# VL6180_Sensor.net
KiCad netlist of a schematic drawn in EAGLE
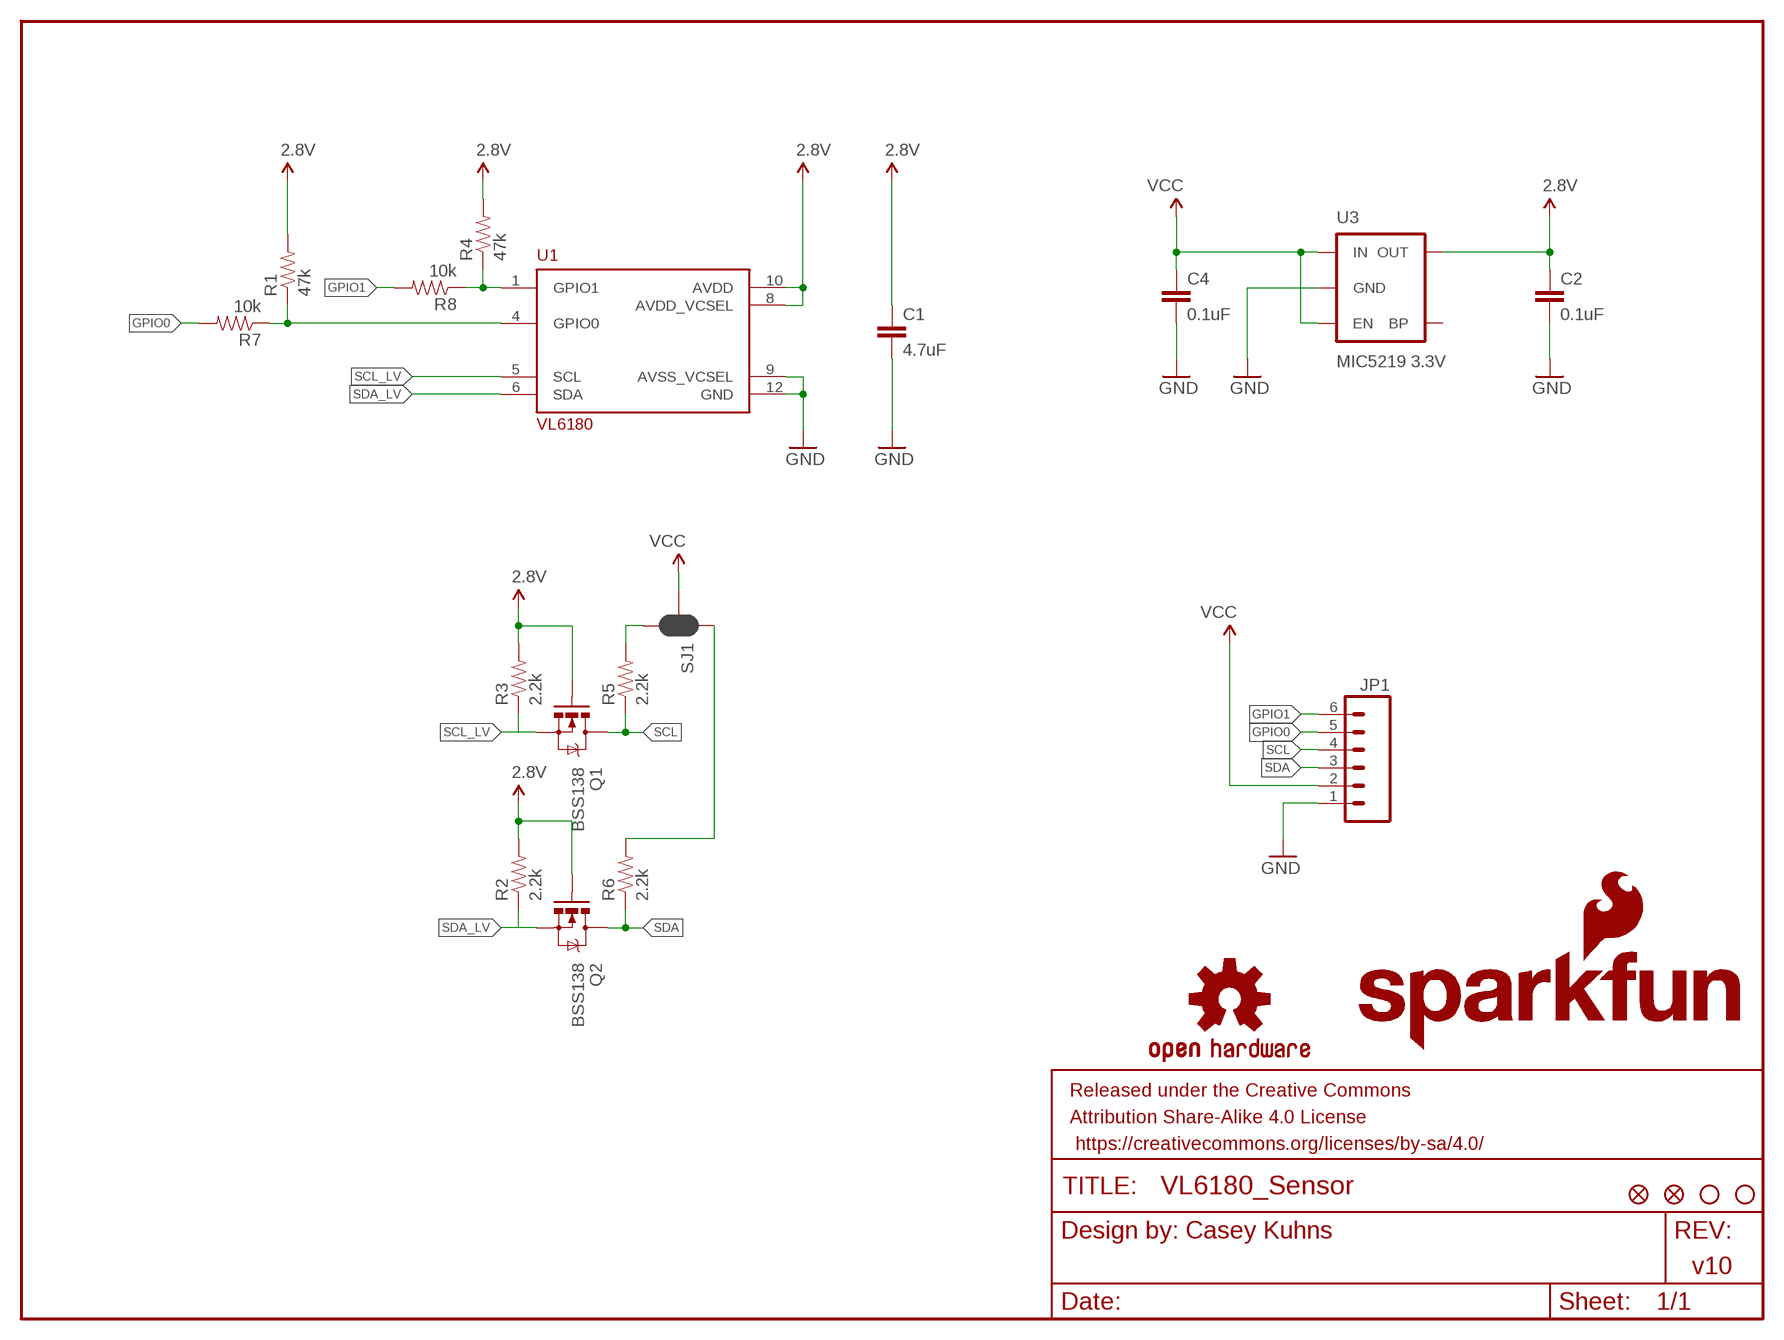
[diagram p0: schematic, sheet 1]

(export (version "E")
  (design (tool "Eeschema 10.0.6"))
  (components
    (comp (ref "C1")
      (value "4.7uF")
      (footprint "eagle-import:0603-CAP")
      (libsource (lib "eagle-import") (part "4.7UF-6.3V-10%(0603)0603"))
    )
    (comp (ref "C2")
      (value "0.1uF")
      (footprint "eagle-import:0603-CAP")
      (libsource (lib "eagle-import") (part "0.1UF-25V(+80/-20%)(0603)"))
    )
    (comp (ref "C4")
      (value "0.1uF")
      (footprint "eagle-import:0603-CAP")
      (libsource (lib "eagle-import") (part "0.1UF-25V(+80/-20%)(0603)"))
    )
    (comp (ref "FID1")
      (value "FIDUCIAL1X2")
      (footprint "eagle-import:FIDUCIAL-1X2")
      (libsource (lib "eagle-import") (part "FIDUCIAL1X2"))
    )
    (comp (ref "FID2")
      (value "FIDUCIAL1X2")
      (footprint "eagle-import:FIDUCIAL-1X2")
      (libsource (lib "eagle-import") (part "FIDUCIAL1X2"))
    )
    (comp (ref "FRAME1")
      (value "FRAME-LETTER")
      (footprint "eagle-import:CREATIVE_COMMONS")
      (libsource (lib "eagle-import") (part "FRAME-LETTER"))
    )
    (comp (ref "JP1")
      (value "M06SIP")
      (footprint "eagle-import:1X06")
      (libsource (lib "eagle-import") (part "M06SIP"))
    )
    (comp (ref "LOGO1")
      (value "SFE_LOGO_NAME_FLAME.1_INCH")
      (footprint "eagle-import:SFE_LOGO_NAME_FLAME_.1")
      (libsource (lib "eagle-import") (part "SFE_LOGO_NAME_FLAME.1_INCH"))
    )
    (comp (ref "LOGO2")
      (value "OSHW-LOGOS")
      (footprint "eagle-import:OSHW-LOGO-S")
      (libsource (lib "eagle-import") (part "OSHW-LOGOS"))
    )
    (comp (ref "Q1")
      (value "BSS138")
      (footprint "eagle-import:SOT23")
      (libsource (lib "eagle-import") (part "MOSFET-NCHANNELBSS138"))
    )
    (comp (ref "Q2")
      (value "BSS138")
      (footprint "eagle-import:SOT23")
      (libsource (lib "eagle-import") (part "MOSFET-NCHANNELBSS138"))
    )
    (comp (ref "R1")
      (value "47k")
      (footprint "eagle-import:0603-RES")
      (libsource (lib "eagle-import") (part "47KOHM1/10W1%(0603)"))
    )
    (comp (ref "R2")
      (value "2.2k")
      (footprint "eagle-import:0603-RES")
      (libsource (lib "eagle-import") (part "2.2KOHM1/10W1%(0603)"))
    )
    (comp (ref "R3")
      (value "2.2k")
      (footprint "eagle-import:0603-RES")
      (libsource (lib "eagle-import") (part "2.2KOHM1/10W1%(0603)"))
    )
    (comp (ref "R4")
      (value "47k")
      (footprint "eagle-import:0603-RES")
      (libsource (lib "eagle-import") (part "47KOHM1/10W1%(0603)"))
    )
    (comp (ref "R5")
      (value "2.2k")
      (footprint "eagle-import:0603-RES")
      (libsource (lib "eagle-import") (part "2.2KOHM1/10W1%(0603)"))
    )
    (comp (ref "R6")
      (value "2.2k")
      (footprint "eagle-import:0603-RES")
      (libsource (lib "eagle-import") (part "2.2KOHM1/10W1%(0603)"))
    )
    (comp (ref "R7")
      (value "10k")
      (footprint "eagle-import:0603-RES")
      (libsource (lib "eagle-import") (part "10KOHM1/10W1%(0603)0603"))
    )
    (comp (ref "R8")
      (value "10k")
      (footprint "eagle-import:0603-RES")
      (libsource (lib "eagle-import") (part "10KOHM1/10W1%(0603)0603"))
    )
    (comp (ref "SJ1")
      (value "JUMPER-PAD-3-NC_BY_PASTE")
      (footprint "eagle-import:PAD-JUMPER-3-NC_BY_PASTE_YES_SILK_FULL_BOX")
      (libsource (lib "eagle-import") (part "JUMPER-PAD-3-NC_BY_PASTE"))
    )
    (comp (ref "STANDOFF1")
      (value "STAND-OFF")
      (footprint "eagle-import:STAND-OFF")
      (libsource (lib "eagle-import") (part "STAND-OFF"))
    )
    (comp (ref "STANDOFF2")
      (value "STAND-OFF")
      (footprint "eagle-import:STAND-OFF")
      (libsource (lib "eagle-import") (part "STAND-OFF"))
    )
    (comp (ref "U1")
      (value "VL6180")
      (footprint "eagle-import:VL6180")
      (libsource (lib "eagle-import") (part "VL6180"))
    )
    (comp (ref "U3")
      (value "MIC5219 3.3V")
      (footprint "eagle-import:SOT23-5")
      (libsource (lib "eagle-import") (part "V_REG_MIC52193.3V"))
    )
  )
  (nets
    (net (code "1") (name "2.8V") (class "Default")
      (node (ref "C1") (pin "1") (pinfunction "1_1") (pintype "passive"))
      (node (ref "C2") (pin "1") (pinfunction "1_1") (pintype "passive"))
      (node (ref "Q1") (pin "1") (pinfunction "G_1") (pintype "passive"))
      (node (ref "Q2") (pin "1") (pinfunction "G_1") (pintype "passive"))
      (node (ref "R1") (pin "2") (pinfunction "2_2") (pintype "passive"))
      (node (ref "R2") (pin "2") (pinfunction "2_2") (pintype "passive"))
      (node (ref "R3") (pin "2") (pinfunction "2_2") (pintype "passive"))
      (node (ref "R4") (pin "2") (pinfunction "2_2") (pintype "passive"))
      (node (ref "U1") (pin "10") (pinfunction "AVDD_10") (pintype "bidirectional"))
      (node (ref "U1") (pin "8") (pinfunction "AVDD_VCSEL_8") (pintype "bidirectional"))
      (node (ref "U3") (pin "5") (pinfunction "OUT_5") (pintype "passive"))
    )
    (net (code "2") (name "GND") (class "Default")
      (node (ref "C1") (pin "2") (pinfunction "2_2") (pintype "passive"))
      (node (ref "C2") (pin "2") (pinfunction "2_2") (pintype "passive"))
      (node (ref "C4") (pin "2") (pinfunction "2_2") (pintype "passive"))
      (node (ref "JP1") (pin "1") (pinfunction "1_1") (pintype "passive"))
      (node (ref "U1") (pin "12") (pinfunction "GND_12") (pintype "bidirectional"))
      (node (ref "U1") (pin "9") (pinfunction "AVSS_VCSEL_9") (pintype "bidirectional"))
      (node (ref "U3") (pin "2") (pinfunction "GND_2") (pintype "input"))
    )
    (net (code "3") (name "GPIO0") (class "Default")
      (node (ref "JP1") (pin "5") (pinfunction "5_5") (pintype "passive"))
      (node (ref "R7") (pin "2") (pinfunction "2_2") (pintype "passive"))
    )
    (net (code "4") (name "GPIO1") (class "Default")
      (node (ref "JP1") (pin "6") (pinfunction "6_6") (pintype "passive"))
      (node (ref "R8") (pin "2") (pinfunction "2_2") (pintype "passive"))
    )
    (net (code "5") (name "Net-(R5-Pad2)") (class "Default")
      (node (ref "R5") (pin "2") (pinfunction "2_2") (pintype "passive"))
      (node (ref "SJ1") (pin "3") (pinfunction "3_3") (pintype "passive"))
    )
    (net (code "6") (name "Net-(R6-Pad2)") (class "Default")
      (node (ref "R6") (pin "2") (pinfunction "2_2") (pintype "passive"))
      (node (ref "SJ1") (pin "1") (pinfunction "1_1") (pintype "passive"))
    )
    (net (code "7") (name "Net-(U1-GPIO0)") (class "Default")
      (node (ref "R1") (pin "1") (pinfunction "1_1") (pintype "passive"))
      (node (ref "R7") (pin "1") (pinfunction "1_1") (pintype "passive"))
      (node (ref "U1") (pin "4") (pinfunction "GPIO0_4") (pintype "bidirectional"))
    )
    (net (code "8") (name "Net-(U1-GPIO1)") (class "Default")
      (node (ref "R4") (pin "1") (pinfunction "1_1") (pintype "passive"))
      (node (ref "R8") (pin "1") (pinfunction "1_1") (pintype "passive"))
      (node (ref "U1") (pin "1") (pinfunction "GPIO1_1") (pintype "bidirectional"))
    )
    (net (code "9") (name "SCL") (class "Default")
      (node (ref "JP1") (pin "4") (pinfunction "4_4") (pintype "passive"))
      (node (ref "Q1") (pin "3") (pinfunction "D_3") (pintype "passive"))
      (node (ref "R5") (pin "1") (pinfunction "1_1") (pintype "passive"))
    )
    (net (code "10") (name "SCL_LV") (class "Default")
      (node (ref "Q1") (pin "2") (pinfunction "S_2") (pintype "passive"))
      (node (ref "R3") (pin "1") (pinfunction "1_1") (pintype "passive"))
      (node (ref "U1") (pin "5") (pinfunction "SCL_5") (pintype "bidirectional"))
    )
    (net (code "11") (name "SDA") (class "Default")
      (node (ref "JP1") (pin "3") (pinfunction "3_3") (pintype "passive"))
      (node (ref "Q2") (pin "3") (pinfunction "D_3") (pintype "passive"))
      (node (ref "R6") (pin "1") (pinfunction "1_1") (pintype "passive"))
    )
    (net (code "12") (name "SDA_LV") (class "Default")
      (node (ref "Q2") (pin "2") (pinfunction "S_2") (pintype "passive"))
      (node (ref "R2") (pin "1") (pinfunction "1_1") (pintype "passive"))
      (node (ref "U1") (pin "6") (pinfunction "SDA_6") (pintype "bidirectional"))
    )
    (net (code "13") (name "VCC") (class "Default")
      (node (ref "C4") (pin "1") (pinfunction "1_1") (pintype "passive"))
      (node (ref "JP1") (pin "2") (pinfunction "2_2") (pintype "passive"))
      (node (ref "SJ1") (pin "2") (pinfunction "2_2") (pintype "passive"))
      (node (ref "U3") (pin "1") (pinfunction "IN_1") (pintype "input"))
      (node (ref "U3") (pin "3") (pinfunction "EN_3") (pintype "input"))
    )
    (net (code "14") (name "unconnected-(U3-BP-Pad4)") (class "Default")
      (node (ref "U3") (pin "4") (pinfunction "BP_4") (pintype "input"))
    )
  )
)
